# Castle_2_3_1_103113.net
KiCad netlist of a schematic drawn in EAGLE
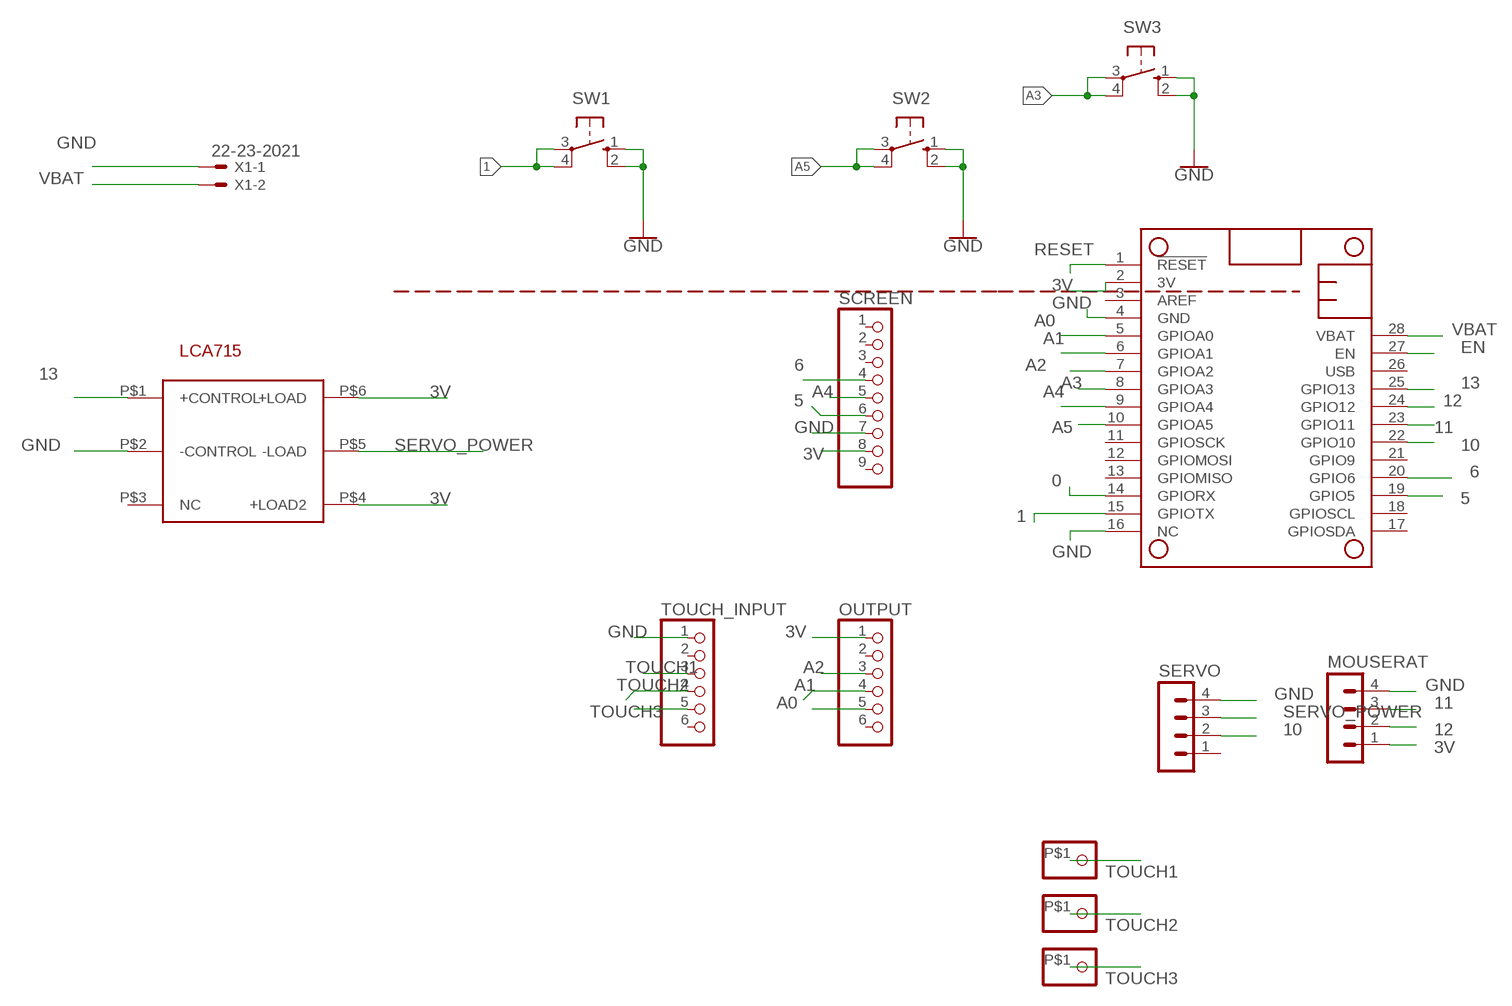
[diagram p0: schematic, sheet 1]

(export (version "E")
  (design (tool "Eeschema 10.0.6"))
  (components
    (comp (ref "EXTRAGND")
      (value "PINHD-1X1-BIGPOGO")
      (footprint "eagle-import:1X1-BIGPOGO")
      (libsource (lib "eagle-import") (part "PINHD-1X1-BIGPOGO"))
    )
    (comp (ref "EXTRAGND1")
      (value "PINHD-1X1-BIGPOGO")
      (footprint "eagle-import:1X1-BIGPOGO")
      (libsource (lib "eagle-import") (part "PINHD-1X1-BIGPOGO"))
    )
    (comp (ref "EXTRAGND2")
      (value "PINHD-1X1-BIGPOGO")
      (footprint "eagle-import:1X1-BIGPOGO")
      (libsource (lib "eagle-import") (part "PINHD-1X1-BIGPOGO"))
    )
    (comp (ref "LCA715")
      (value "LCA715S")
      (footprint "eagle-import:LCA7XX")
      (libsource (lib "eagle-import") (part "LCA715S"))
    )
    (comp (ref "MOUSERAT")
      (value "MA04-1")
      (footprint "eagle-import:MA04-1")
      (libsource (lib "eagle-import") (part "MA04-1"))
    )
    (comp (ref "MS2")
      (value "FEATHERWING_NODIM")
      (footprint "eagle-import:FEATHERWING_DIM")
      (libsource (lib "eagle-import") (part "FEATHERWING_NODIM"))
    )
    (comp (ref "OUTPUT")
      (value "PINHD-1X6")
      (footprint "eagle-import:1X06")
      (libsource (lib "eagle-import") (part "PINHD-1X6"))
    )
    (comp (ref "SCREEN")
      (value "PINHD-1X9")
      (footprint "eagle-import:1X09-BIG")
      (libsource (lib "eagle-import") (part "PINHD-1X9"))
    )
    (comp (ref "SERVO")
      (value "MA04-1")
      (footprint "eagle-import:MA04-1")
      (libsource (lib "eagle-import") (part "MA04-1"))
    )
    (comp (ref "SW1")
      (value "10-XX")
      (footprint "eagle-import:B3F-10XX")
      (libsource (lib "eagle-import") (part "10-XX"))
    )
    (comp (ref "SW2")
      (value "10-XX")
      (footprint "eagle-import:B3F-10XX")
      (libsource (lib "eagle-import") (part "10-XX"))
    )
    (comp (ref "SW3")
      (value "10-XX")
      (footprint "eagle-import:B3F-10XX")
      (libsource (lib "eagle-import") (part "10-XX"))
    )
    (comp (ref "TOUCH_INPUT")
      (value "PINHD-1X6")
      (footprint "eagle-import:1X06")
      (libsource (lib "eagle-import") (part "PINHD-1X6"))
    )
    (comp (ref "X1")
      (value "22-23-2021")
      (footprint "eagle-import:22-23-2021")
      (fields (field (name "MF") "MOLEX"))
      (libsource (lib "eagle-import") (part "22-23-2021"))
    )
  )
  (nets
    (net (code "1") (name "/0") (class "Default")
      (node (ref "MS2") (pin "14") (pinfunction "GPIORX_14") (pintype "bidirectional"))
    )
    (net (code "2") (name "/3V") (class "Default")
      (node (ref "LCA715") (pin "P$4") (pinfunction "+LOAD2_P$4") (pintype "bidirectional"))
      (node (ref "LCA715") (pin "P$6") (pinfunction "+LOAD_P$6") (pintype "bidirectional"))
      (node (ref "MOUSERAT") (pin "1") (pinfunction "1_1") (pintype "passive"))
      (node (ref "MS2") (pin "2") (pinfunction "3V_2") (pintype "power_in"))
      (node (ref "OUTPUT") (pin "1") (pinfunction "1_1") (pintype "passive"))
      (node (ref "SCREEN") (pin "8") (pinfunction "8_8") (pintype "passive"))
    )
    (net (code "3") (name "/5") (class "Default")
      (node (ref "MS2") (pin "19") (pinfunction "GPIO5_19") (pintype "bidirectional"))
      (node (ref "SCREEN") (pin "6") (pinfunction "6_6") (pintype "passive"))
    )
    (net (code "4") (name "/6") (class "Default")
      (node (ref "MS2") (pin "20") (pinfunction "GPIO6_20") (pintype "bidirectional"))
      (node (ref "SCREEN") (pin "4") (pinfunction "4_4") (pintype "passive"))
    )
    (net (code "5") (name "/10") (class "Default")
      (node (ref "MS2") (pin "22") (pinfunction "GPIO10_22") (pintype "bidirectional"))
      (node (ref "SERVO") (pin "2") (pinfunction "2_2") (pintype "passive"))
    )
    (net (code "6") (name "/11") (class "Default")
      (node (ref "MOUSERAT") (pin "3") (pinfunction "3_3") (pintype "passive"))
      (node (ref "MS2") (pin "23") (pinfunction "GPIO11_23") (pintype "bidirectional"))
    )
    (net (code "7") (name "/12") (class "Default")
      (node (ref "MOUSERAT") (pin "2") (pinfunction "2_2") (pintype "passive"))
      (node (ref "MS2") (pin "24") (pinfunction "GPIO12_24") (pintype "bidirectional"))
    )
    (net (code "8") (name "/13") (class "Default")
      (node (ref "LCA715") (pin "P$1") (pinfunction "+CONTROL_P$1") (pintype "bidirectional"))
      (node (ref "MS2") (pin "25") (pinfunction "GPIO13_25") (pintype "bidirectional"))
    )
    (net (code "9") (name "/A0") (class "Default")
      (node (ref "MS2") (pin "5") (pinfunction "GPIOA0_5") (pintype "bidirectional"))
      (node (ref "OUTPUT") (pin "5") (pinfunction "5_5") (pintype "passive"))
    )
    (net (code "10") (name "/A1") (class "Default")
      (node (ref "MS2") (pin "6") (pinfunction "GPIOA1_6") (pintype "bidirectional"))
      (node (ref "OUTPUT") (pin "4") (pinfunction "4_4") (pintype "passive"))
    )
    (net (code "11") (name "/A2") (class "Default")
      (node (ref "MS2") (pin "7") (pinfunction "GPIOA2_7") (pintype "bidirectional"))
      (node (ref "OUTPUT") (pin "3") (pinfunction "3_3") (pintype "passive"))
    )
    (net (code "12") (name "/A4") (class "Default")
      (node (ref "MS2") (pin "9") (pinfunction "GPIOA4_9") (pintype "bidirectional"))
      (node (ref "SCREEN") (pin "5") (pinfunction "5_5") (pintype "passive"))
    )
    (net (code "13") (name "/EN") (class "Default")
      (node (ref "MS2") (pin "27") (pinfunction "EN_27") (pintype "passive"))
    )
    (net (code "14") (name "/RESET") (class "Default")
      (node (ref "MS2") (pin "1") (pinfunction "~{RESET}_1") (pintype "input"))
    )
    (net (code "15") (name "/SERVO_POWER") (class "Default")
      (node (ref "LCA715") (pin "P$5") (pinfunction "-LOAD_P$5") (pintype "bidirectional"))
      (node (ref "SERVO") (pin "3") (pinfunction "3_3") (pintype "passive"))
    )
    (net (code "16") (name "/TOUCH1") (class "Default")
      (node (ref "EXTRAGND") (pin "P$1") (pinfunction "1_P$1") (pintype "passive"))
      (node (ref "TOUCH_INPUT") (pin "3") (pinfunction "3_3") (pintype "passive"))
    )
    (net (code "17") (name "/TOUCH2") (class "Default")
      (node (ref "EXTRAGND1") (pin "P$1") (pinfunction "1_P$1") (pintype "passive"))
      (node (ref "TOUCH_INPUT") (pin "4") (pinfunction "4_4") (pintype "passive"))
    )
    (net (code "18") (name "/TOUCH3") (class "Default")
      (node (ref "EXTRAGND2") (pin "P$1") (pinfunction "1_P$1") (pintype "passive"))
      (node (ref "TOUCH_INPUT") (pin "5") (pinfunction "5_5") (pintype "passive"))
    )
    (net (code "19") (name "/USB") (class "Default")
      (node (ref "MS2") (pin "26") (pinfunction "USB_26") (pintype "power_in"))
    )
    (net (code "20") (name "/VBAT") (class "Default")
      (node (ref "MS2") (pin "28") (pinfunction "VBAT_28") (pintype "power_in"))
      (node (ref "X1") (pin "2") (pinfunction "S_2") (pintype "passive"))
    )
    (net (code "21") (name "1") (class "Default")
      (node (ref "MS2") (pin "15") (pinfunction "GPIOTX_15") (pintype "bidirectional"))
      (node (ref "SW1") (pin "3") (pinfunction "P_3") (pintype "passive"))
      (node (ref "SW1") (pin "4") (pinfunction "P1_4") (pintype "passive"))
    )
    (net (code "22") (name "A3") (class "Default")
      (node (ref "MS2") (pin "8") (pinfunction "GPIOA3_8") (pintype "bidirectional"))
      (node (ref "SW3") (pin "3") (pinfunction "P_3") (pintype "passive"))
      (node (ref "SW3") (pin "4") (pinfunction "P1_4") (pintype "passive"))
    )
    (net (code "23") (name "A5") (class "Default")
      (node (ref "MS2") (pin "10") (pinfunction "GPIOA5_10") (pintype "bidirectional"))
      (node (ref "SW2") (pin "3") (pinfunction "P_3") (pintype "passive"))
      (node (ref "SW2") (pin "4") (pinfunction "P1_4") (pintype "passive"))
    )
    (net (code "24") (name "GND") (class "Default")
      (node (ref "LCA715") (pin "P$2") (pinfunction "-CONTROL_P$2") (pintype "bidirectional"))
      (node (ref "MOUSERAT") (pin "4") (pinfunction "4_4") (pintype "passive"))
      (node (ref "MS2") (pin "16") (pinfunction "NC_16") (pintype "passive"))
      (node (ref "MS2") (pin "4") (pinfunction "GND_4") (pintype "power_in"))
      (node (ref "SCREEN") (pin "7") (pinfunction "7_7") (pintype "passive"))
      (node (ref "SERVO") (pin "4") (pinfunction "4_4") (pintype "passive"))
      (node (ref "SW1") (pin "1") (pinfunction "S_1") (pintype "passive"))
      (node (ref "SW1") (pin "2") (pinfunction "S1_2") (pintype "passive"))
      (node (ref "SW2") (pin "1") (pinfunction "S_1") (pintype "passive"))
      (node (ref "SW2") (pin "2") (pinfunction "S1_2") (pintype "passive"))
      (node (ref "SW3") (pin "1") (pinfunction "S_1") (pintype "passive"))
      (node (ref "SW3") (pin "2") (pinfunction "S1_2") (pintype "passive"))
      (node (ref "TOUCH_INPUT") (pin "1") (pinfunction "1_1") (pintype "passive"))
      (node (ref "X1") (pin "1") (pinfunction "S_1") (pintype "passive"))
    )
    (net (code "25") (name "unconnected-(LCA715-NC-PadP$3)") (class "Default")
      (node (ref "LCA715") (pin "P$3") (pinfunction "NC_P$3") (pintype "bidirectional"))
    )
    (net (code "26") (name "unconnected-(MS2-AREF-Pad3)") (class "Default")
      (node (ref "MS2") (pin "3") (pinfunction "AREF_3") (pintype "passive"))
    )
    (net (code "27") (name "unconnected-(MS2-GPIO9-Pad21)") (class "Default")
      (node (ref "MS2") (pin "21") (pinfunction "GPIO9_21") (pintype "bidirectional"))
    )
    (net (code "28") (name "unconnected-(MS2-GPIOMISO-Pad13)") (class "Default")
      (node (ref "MS2") (pin "13") (pinfunction "GPIOMISO_13") (pintype "bidirectional"))
    )
    (net (code "29") (name "unconnected-(MS2-GPIOMOSI-Pad12)") (class "Default")
      (node (ref "MS2") (pin "12") (pinfunction "GPIOMOSI_12") (pintype "bidirectional"))
    )
    (net (code "30") (name "unconnected-(MS2-GPIOSCK-Pad11)") (class "Default")
      (node (ref "MS2") (pin "11") (pinfunction "GPIOSCK_11") (pintype "bidirectional"))
    )
    (net (code "31") (name "unconnected-(MS2-GPIOSCL-Pad18)") (class "Default")
      (node (ref "MS2") (pin "18") (pinfunction "GPIOSCL_18") (pintype "bidirectional"))
    )
    (net (code "32") (name "unconnected-(MS2-GPIOSDA-Pad17)") (class "Default")
      (node (ref "MS2") (pin "17") (pinfunction "GPIOSDA_17") (pintype "bidirectional"))
    )
    (net (code "33") (name "unconnected-(OUTPUT-Pad2)") (class "Default")
      (node (ref "OUTPUT") (pin "2") (pinfunction "2_2") (pintype "passive"))
    )
    (net (code "34") (name "unconnected-(OUTPUT-Pad6)") (class "Default")
      (node (ref "OUTPUT") (pin "6") (pinfunction "6_6") (pintype "passive"))
    )
    (net (code "35") (name "unconnected-(SCREEN-Pad1)") (class "Default")
      (node (ref "SCREEN") (pin "1") (pinfunction "1_1") (pintype "passive"))
    )
    (net (code "36") (name "unconnected-(SCREEN-Pad2)") (class "Default")
      (node (ref "SCREEN") (pin "2") (pinfunction "2_2") (pintype "passive"))
    )
    (net (code "37") (name "unconnected-(SCREEN-Pad3)") (class "Default")
      (node (ref "SCREEN") (pin "3") (pinfunction "3_3") (pintype "passive"))
    )
    (net (code "38") (name "unconnected-(SCREEN-Pad9)") (class "Default")
      (node (ref "SCREEN") (pin "9") (pinfunction "9_9") (pintype "passive"))
    )
    (net (code "39") (name "unconnected-(SERVO-Pad1)") (class "Default")
      (node (ref "SERVO") (pin "1") (pinfunction "1_1") (pintype "passive"))
    )
    (net (code "40") (name "unconnected-(TOUCH_INPUT-Pad2)") (class "Default")
      (node (ref "TOUCH_INPUT") (pin "2") (pinfunction "2_2") (pintype "passive"))
    )
    (net (code "41") (name "unconnected-(TOUCH_INPUT-Pad6)") (class "Default")
      (node (ref "TOUCH_INPUT") (pin "6") (pinfunction "6_6") (pintype "passive"))
    )
  )
)
